# usb-eeprom.net
KiCad netlist of a schematic drawn in EAGLE
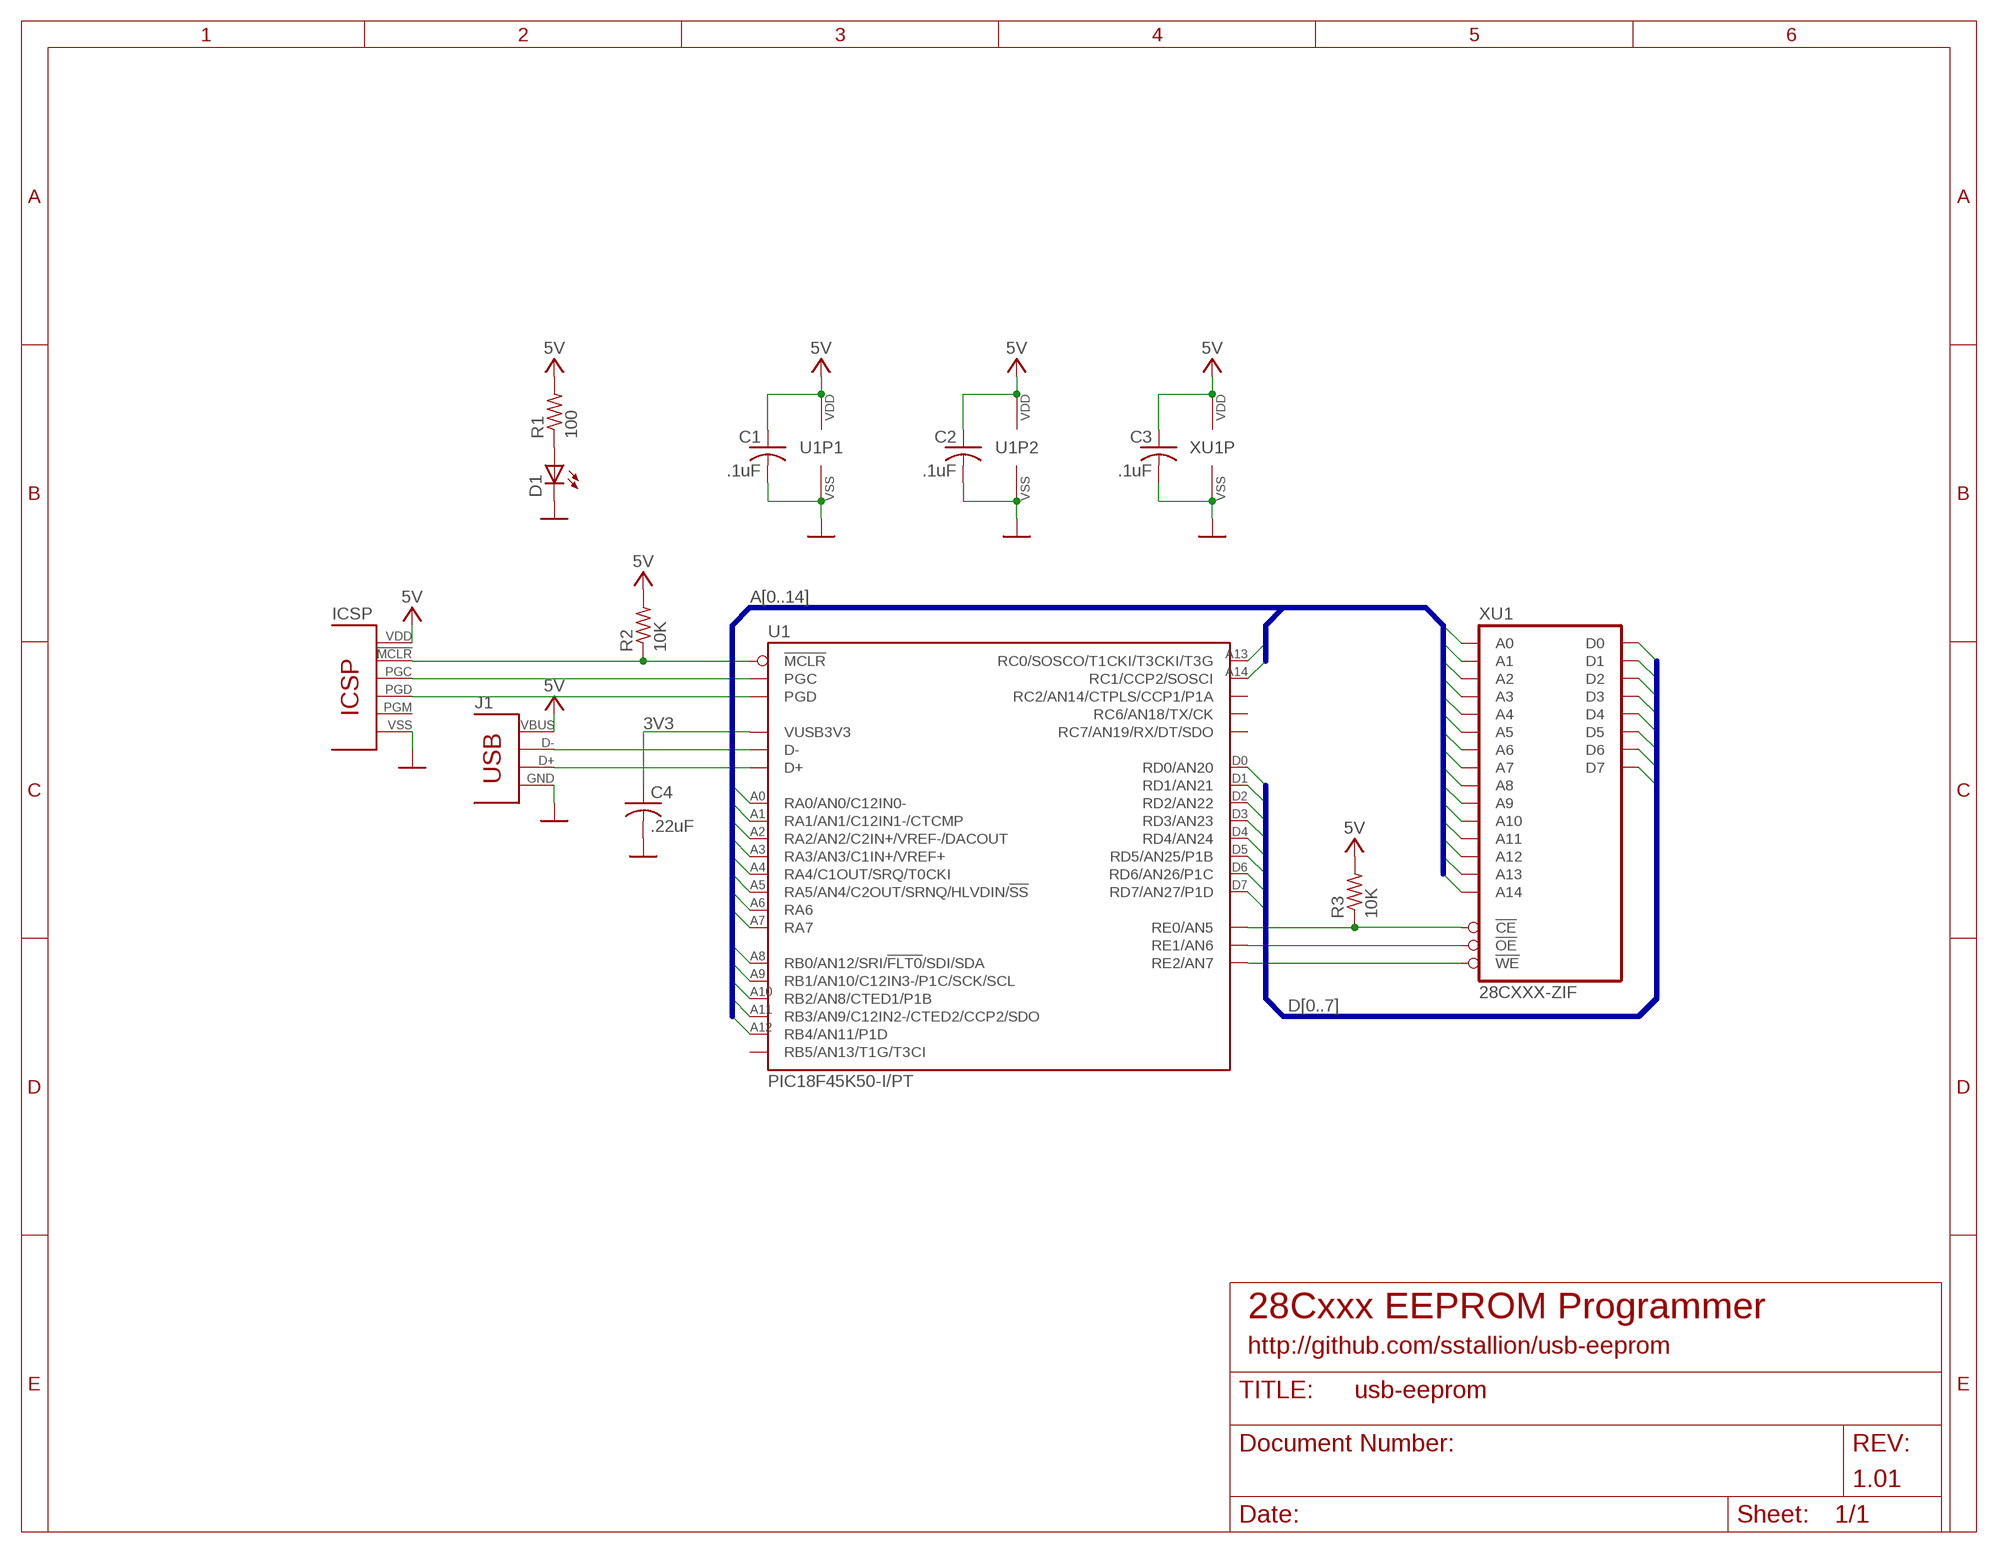
[diagram p0: schematic, sheet 1]

(export (version "E")
  (design (tool "Eeschema 10.0.6"))
  (components
    (comp (ref "C1")
      (value ".1uF")
      (footprint "eagle-import:C0805")
      (fields (field (name "MFG") "Vishay"))
      (libsource (lib "eagle-import") (part "C-USC0805"))
    )
    (comp (ref "C2")
      (value ".1uF")
      (footprint "eagle-import:C0805")
      (fields (field (name "MFG") "Vishay"))
      (libsource (lib "eagle-import") (part "C-USC0805"))
    )
    (comp (ref "C3")
      (value ".1uF")
      (footprint "eagle-import:C0805")
      (fields (field (name "MFG") "Vishay"))
      (libsource (lib "eagle-import") (part "C-USC0805"))
    )
    (comp (ref "C4")
      (value ".22uF")
      (footprint "eagle-import:C0805")
      (fields (field (name "MFG") "Vishay"))
      (libsource (lib "eagle-import") (part "C-USC0805"))
    )
    (comp (ref "D1")
      (value "BLUE")
      (footprint "eagle-import:SML0805")
      (fields (field (name "MFG") "Kingbright"))
      (libsource (lib "eagle-import") (part "LEDSML0805"))
    )
    (comp (ref "ICSP")
      (value "ICSP")
      (footprint "eagle-import:ICSP")
      (libsource (lib "eagle-import") (part "ICSP"))
    )
    (comp (ref "J1")
      (value "USBA")
      (footprint "eagle-import:USBA")
      (fields (field (name "MFG") "Molex"))
      (libsource (lib "eagle-import") (part "USBA"))
    )
    (comp (ref "R1")
      (value "100")
      (footprint "eagle-import:R0805")
      (fields (field (name "MFG") "Vishay"))
      (libsource (lib "eagle-import") (part "R-US_R0805"))
    )
    (comp (ref "R2")
      (value "10K")
      (footprint "eagle-import:R0805")
      (fields (field (name "MFG") "Vishay"))
      (libsource (lib "eagle-import") (part "R-US_R0805"))
    )
    (comp (ref "R3")
      (value "10K")
      (footprint "eagle-import:R0805")
      (fields (field (name "MFG") "Vishay"))
      (libsource (lib "eagle-import") (part "R-US_R0805"))
    )
    (comp (ref "U1")
      (value "PIC18F45K50-I/PT")
      (footprint "eagle-import:TQFP44")
      (fields
        (field (name "MFG") "Microchip Technology")
        (field (name "MFG_PN") "PIC18F45K50-I/PT")
        (field (name "MOUSER_PN") "579-PIC18F45K50-I/PT")
        (field (name "NOTES") "48MHz 32KB FLASH 2KB RAM")
      )
      (libsource (lib "eagle-import") (part "PIC18F45K50-I/PT"))
    )
    (comp (ref "XU1")
      (value "28CXXX-ZIF")
      (footprint "eagle-import:ZIF28")
      (fields
        (field (name "MFG") "3M")
        (field (name "MFG_PN") "228-1371-00-0602J")
        (field (name "MOUSER_PN") "517-228-1371-00")
        (field (name "NOTES") "28 PIN ZIF SOCKET")
      )
      (libsource (lib "eagle-import") (part "28CXXX-ZIF"))
    )
  )
  (nets
    (net (code "1") (name "/A0") (class "Default")
      (node (ref "U1") (pin "19") (pinfunction "RA0/AN0/C12IN0-_19") (pintype "bidirectional"))
      (node (ref "XU1") (pin "10") (pinfunction "A0_10") (pintype "input"))
    )
    (net (code "2") (name "/A1") (class "Default")
      (node (ref "U1") (pin "20") (pinfunction "RA1/AN1/C12IN1-/CTCMP_20") (pintype "bidirectional"))
      (node (ref "XU1") (pin "9") (pinfunction "A1_9") (pintype "input"))
    )
    (net (code "3") (name "/A2") (class "Default")
      (node (ref "U1") (pin "21") (pinfunction "RA2/AN2/C2IN+/VREF-/DACOUT_21") (pintype "bidirectional"))
      (node (ref "XU1") (pin "8") (pinfunction "A2_8") (pintype "input"))
    )
    (net (code "4") (name "/A3") (class "Default")
      (node (ref "U1") (pin "22") (pinfunction "RA3/AN3/C1IN+/VREF+_22") (pintype "bidirectional"))
      (node (ref "XU1") (pin "7") (pinfunction "A3_7") (pintype "input"))
    )
    (net (code "5") (name "/A4") (class "Default")
      (node (ref "U1") (pin "23") (pinfunction "RA4/C1OUT/SRQ/T0CKI_23") (pintype "bidirectional"))
      (node (ref "XU1") (pin "6") (pinfunction "A4_6") (pintype "input"))
    )
    (net (code "6") (name "/A5") (class "Default")
      (node (ref "U1") (pin "24") (pinfunction "RA5/AN4/C2OUT/SRNQ/HLVDIN/~{SS}_24") (pintype "bidirectional"))
      (node (ref "XU1") (pin "5") (pinfunction "A5_5") (pintype "input"))
    )
    (net (code "7") (name "/A6") (class "Default")
      (node (ref "U1") (pin "31") (pinfunction "RA6_31") (pintype "bidirectional"))
      (node (ref "XU1") (pin "4") (pinfunction "A6_4") (pintype "input"))
    )
    (net (code "8") (name "/A7") (class "Default")
      (node (ref "U1") (pin "30") (pinfunction "RA7_30") (pintype "bidirectional"))
      (node (ref "XU1") (pin "3") (pinfunction "A7_3") (pintype "input"))
    )
    (net (code "9") (name "/A8") (class "Default")
      (node (ref "U1") (pin "8") (pinfunction "RB0/AN12/SRI/~{FLT0}/SDI/SDA_8") (pintype "bidirectional"))
      (node (ref "XU1") (pin "25") (pinfunction "A8_25") (pintype "input"))
    )
    (net (code "10") (name "/A9") (class "Default")
      (node (ref "U1") (pin "9") (pinfunction "RB1/AN10/C12IN3-/P1C/SCK/SCL_9") (pintype "bidirectional"))
      (node (ref "XU1") (pin "24") (pinfunction "A9_24") (pintype "input"))
    )
    (net (code "11") (name "/A10") (class "Default")
      (node (ref "U1") (pin "10") (pinfunction "RB2/AN8/CTED1/P1B_10") (pintype "bidirectional"))
      (node (ref "XU1") (pin "21") (pinfunction "A10_21") (pintype "input"))
    )
    (net (code "12") (name "/A11") (class "Default")
      (node (ref "U1") (pin "11") (pinfunction "RB3/AN9/C12IN2-/CTED2/CCP2/SDO_11") (pintype "bidirectional"))
      (node (ref "XU1") (pin "23") (pinfunction "A11_23") (pintype "input"))
    )
    (net (code "13") (name "/A12") (class "Default")
      (node (ref "U1") (pin "14") (pinfunction "RB4/AN11/P1D_14") (pintype "bidirectional"))
      (node (ref "XU1") (pin "2") (pinfunction "A12_2") (pintype "input"))
    )
    (net (code "14") (name "/A13") (class "Default")
      (node (ref "U1") (pin "32") (pinfunction "RC0/SOSCO/T1CKI/T3CKI/T3G_32") (pintype "bidirectional"))
      (node (ref "XU1") (pin "26") (pinfunction "A13_26") (pintype "input"))
    )
    (net (code "15") (name "/A14") (class "Default")
      (node (ref "U1") (pin "35") (pinfunction "RC1/CCP2/SOSCI_35") (pintype "bidirectional"))
      (node (ref "XU1") (pin "1") (pinfunction "A14_1") (pintype "input"))
    )
    (net (code "17") (name "/D0") (class "Default")
      (node (ref "U1") (pin "38") (pinfunction "RD0/AN20_38") (pintype "bidirectional"))
      (node (ref "XU1") (pin "11") (pinfunction "D0_11") (pintype "bidirectional"))
    )
    (net (code "18") (name "/D1") (class "Default")
      (node (ref "U1") (pin "39") (pinfunction "RD1/AN21_39") (pintype "bidirectional"))
      (node (ref "XU1") (pin "12") (pinfunction "D1_12") (pintype "bidirectional"))
    )
    (net (code "19") (name "/D2") (class "Default")
      (node (ref "U1") (pin "40") (pinfunction "RD2/AN22_40") (pintype "bidirectional"))
      (node (ref "XU1") (pin "13") (pinfunction "D2_13") (pintype "bidirectional"))
    )
    (net (code "20") (name "/D3") (class "Default")
      (node (ref "U1") (pin "41") (pinfunction "RD3/AN23_41") (pintype "bidirectional"))
      (node (ref "XU1") (pin "15") (pinfunction "D3_15") (pintype "bidirectional"))
    )
    (net (code "21") (name "/D4") (class "Default")
      (node (ref "U1") (pin "2") (pinfunction "RD4/AN24_2") (pintype "bidirectional"))
      (node (ref "XU1") (pin "16") (pinfunction "D4_16") (pintype "bidirectional"))
    )
    (net (code "22") (name "/D5") (class "Default")
      (node (ref "U1") (pin "3") (pinfunction "RD5/AN25/P1B_3") (pintype "bidirectional"))
      (node (ref "XU1") (pin "17") (pinfunction "D5_17") (pintype "bidirectional"))
    )
    (net (code "23") (name "/D6") (class "Default")
      (node (ref "U1") (pin "4") (pinfunction "RD6/AN26/P1C_4") (pintype "bidirectional"))
      (node (ref "XU1") (pin "18") (pinfunction "D6_18") (pintype "bidirectional"))
    )
    (net (code "24") (name "/D7") (class "Default")
      (node (ref "U1") (pin "5") (pinfunction "RD7/AN27/P1D_5") (pintype "bidirectional"))
      (node (ref "XU1") (pin "19") (pinfunction "D7_19") (pintype "bidirectional"))
    )
    (net (code "26") (name "5V") (class "Default")
      (node (ref "C1") (pin "1") (pinfunction "1_1") (pintype "passive"))
      (node (ref "C2") (pin "1") (pinfunction "1_1") (pintype "passive"))
      (node (ref "C3") (pin "1") (pinfunction "1_1") (pintype "passive"))
      (node (ref "ICSP") (pin "2") (pinfunction "VDD_2") (pintype "power_in"))
      (node (ref "J1") (pin "1") (pinfunction "1_1") (pintype "power_in"))
      (node (ref "R1") (pin "2") (pinfunction "2_2") (pintype "passive"))
      (node (ref "R2") (pin "2") (pinfunction "2_2") (pintype "passive"))
      (node (ref "R3") (pin "2") (pinfunction "2_2") (pintype "passive"))
      (node (ref "U1") (pin "28") (pinfunction "VDD_28") (pintype "power_in"))
      (node (ref "U1") (pin "7") (pinfunction "VDD_7") (pintype "power_in"))
      (node (ref "XU1") (pin "28") (pinfunction "VDD_28") (pintype "power_in"))
    )
    (net (code "27") (name "GND") (class "Default")
      (node (ref "C1") (pin "2") (pinfunction "2_2") (pintype "passive"))
      (node (ref "C2") (pin "2") (pinfunction "2_2") (pintype "passive"))
      (node (ref "C3") (pin "2") (pinfunction "2_2") (pintype "passive"))
      (node (ref "C4") (pin "2") (pinfunction "2_2") (pintype "passive"))
      (node (ref "D1") (pin "C") (pinfunction "C_C") (pintype "passive"))
      (node (ref "ICSP") (pin "3") (pinfunction "VSS_3") (pintype "power_in"))
      (node (ref "J1") (pin "4") (pinfunction "4_4") (pintype "power_in"))
      (node (ref "J1") (pin "5") (pinfunction "4_5") (pintype "power_in"))
      (node (ref "J1") (pin "6") (pinfunction "4_6") (pintype "power_in"))
      (node (ref "U1") (pin "29") (pinfunction "VSS_29") (pintype "power_in"))
      (node (ref "U1") (pin "6") (pinfunction "VSS_6") (pintype "power_in"))
      (node (ref "XU1") (pin "14") (pinfunction "VSS_14") (pintype "power_in"))
    )
    (net (code "28") (name "Net-(D1-PadA)") (class "Default")
      (node (ref "D1") (pin "A") (pinfunction "A_A") (pintype "passive"))
      (node (ref "R1") (pin "1") (pinfunction "1_1") (pintype "passive"))
    )
    (net (code "29") (name "Net-(ICSP-PGC)") (class "Default")
      (node (ref "ICSP") (pin "5") (pinfunction "PGC_5") (pintype "bidirectional"))
      (node (ref "U1") (pin "16") (pinfunction "PGC_16") (pintype "bidirectional"))
    )
    (net (code "30") (name "Net-(ICSP-PGD)") (class "Default")
      (node (ref "ICSP") (pin "4") (pinfunction "PGD_4") (pintype "bidirectional"))
      (node (ref "U1") (pin "17") (pinfunction "PGD_17") (pintype "bidirectional"))
    )
    (net (code "31") (name "Net-(ICSP-~{MCLR})") (class "Default")
      (node (ref "ICSP") (pin "1") (pinfunction "~{MCLR}_1") (pintype "output"))
      (node (ref "R2") (pin "1") (pinfunction "1_1") (pintype "passive"))
      (node (ref "U1") (pin "18") (pinfunction "~{MCLR}_18") (pintype "input"))
    )
    (net (code "32") (name "Net-(U1A-D+)") (class "Default")
      (node (ref "J1") (pin "3") (pinfunction "3_3") (pintype "bidirectional"))
      (node (ref "U1") (pin "43") (pinfunction "D+_43") (pintype "bidirectional"))
    )
    (net (code "33") (name "Net-(U1A-D-)") (class "Default")
      (node (ref "J1") (pin "2") (pinfunction "2_2") (pintype "bidirectional"))
      (node (ref "U1") (pin "42") (pinfunction "D-_42") (pintype "bidirectional"))
    )
    (net (code "34") (name "Net-(U1A-RE0{slash}AN5)") (class "Default")
      (node (ref "R3") (pin "1") (pinfunction "1_1") (pintype "passive"))
      (node (ref "U1") (pin "25") (pinfunction "RE0/AN5_25") (pintype "bidirectional"))
      (node (ref "XU1") (pin "20") (pinfunction "~{CE}_20") (pintype "input"))
    )
    (net (code "35") (name "Net-(U1A-RE1{slash}AN6)") (class "Default")
      (node (ref "U1") (pin "26") (pinfunction "RE1/AN6_26") (pintype "bidirectional"))
      (node (ref "XU1") (pin "22") (pinfunction "~{OE}_22") (pintype "input"))
    )
    (net (code "36") (name "Net-(U1A-RE2{slash}AN7)") (class "Default")
      (node (ref "U1") (pin "27") (pinfunction "RE2/AN7_27") (pintype "bidirectional"))
      (node (ref "XU1") (pin "27") (pinfunction "~{WE}_27") (pintype "input"))
    )
    (net (code "37") (name "Net-(U1A-VUSB3V3)") (class "Default")
      (node (ref "C4") (pin "1") (pinfunction "1_1") (pintype "passive"))
      (node (ref "U1") (pin "37") (pinfunction "VUSB3V3_37") (pintype "power_in"))
    )
    (net (code "38") (name "unconnected-(ICSP-PGM-Pad6)") (class "Default")
      (node (ref "ICSP") (pin "6") (pinfunction "PGM_6") (pintype "bidirectional"))
    )
    (net (code "39") (name "unconnected-(U1A-RB5{slash}AN13{slash}T1G{slash}T3CI-Pad15)") (class "Default")
      (node (ref "U1") (pin "15") (pinfunction "RB5/AN13/T1G/T3CI_15") (pintype "bidirectional"))
    )
    (net (code "40") (name "unconnected-(U1A-RC2{slash}AN14{slash}CTPLS{slash}CCP1{slash}P1A-Pad36)") (class "Default")
      (node (ref "U1") (pin "36") (pinfunction "RC2/AN14/CTPLS/CCP1/P1A_36") (pintype "bidirectional"))
    )
    (net (code "41") (name "unconnected-(U1A-RC6{slash}AN18{slash}TX{slash}CK-Pad44)") (class "Default")
      (node (ref "U1") (pin "44") (pinfunction "RC6/AN18/TX/CK_44") (pintype "bidirectional"))
    )
    (net (code "42") (name "unconnected-(U1A-RC7{slash}AN19{slash}RX{slash}DT{slash}SDO-Pad1)") (class "Default")
      (node (ref "U1") (pin "1") (pinfunction "RC7/AN19/RX/DT/SDO_1") (pintype "bidirectional"))
    )
  )
)
